# CAN_ChaseCar.net
KiCad netlist of a schematic drawn in Altium Designer
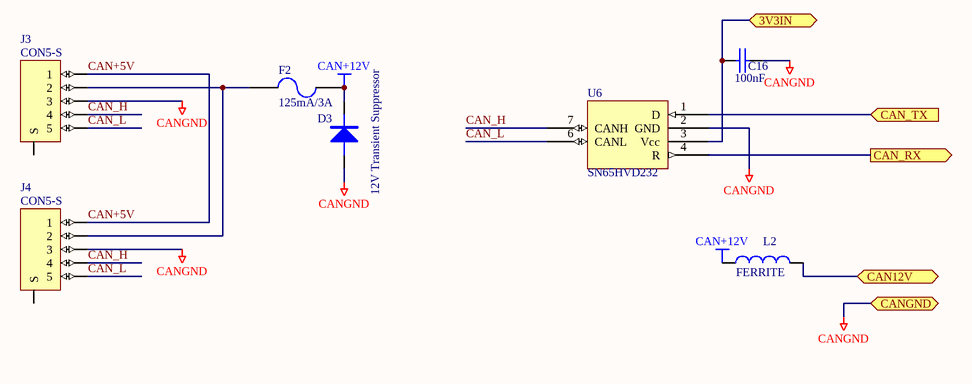
[diagram p0: CAN_ChaseCar.SchDoc]

(export (version "E")
  (design (tool "Eeschema 10.0.6"))
  (components
    (comp (ref "C16")
      (value "100nF")
      (footprint "0603")
      (description "Capacitor")
      (libsource (lib "*") (part "CAP"))
    )
    (comp (ref "D3")
      (value "12V Transient Suppressor")
      (footprint "SMA")
      (description "Diode")
      (libsource (lib "RCLDQ") (part "DIODE"))
    )
    (comp (ref "F2")
      (value "125mA/3A")
      (footprint "LITTELFUSE-154")
      (description "Fuse")
      (libsource (lib "*") (part "FUSE2"))
    )
    (comp (ref "J3")
      (value "CON5-S")
      (footprint "TRIAD5F")
      (description "Connector, 2 pin, with shield @ S")
      (libsource (lib "*") (part "CON5-S"))
    )
    (comp (ref "J4")
      (value "CON5-S")
      (footprint "TRIAD5F")
      (description "Connector, 2 pin, with shield @ S")
      (libsource (lib "*") (part "CON5-S"))
    )
    (comp (ref "L2")
      (value "FERRITE")
      (footprint "0603")
      (description "Inductor")
      (fields (field (name "MANUFACTURER") "Generic Components"))
      (libsource (lib "RCLDQ") (part "INDUCTOR"))
    )
    (comp (ref "U6")
      (value "SN65HVD232")
      (footprint "SO8")
      (description "3.3V CAN Transciever")
      (libsource (lib "*") (part "SN65HVD232"))
    )
  )
  (nets
    (net (code "1") (name "/3V3IN") (class "Default")
      (node (ref "C16") (pin "2") (pinfunction "2_2") (pintype "passive"))
      (node (ref "U6") (pin "3") (pinfunction "Vcc_3") (pintype "power_in"))
    )
    (net (code "2") (name "/CAN+5V") (class "Default")
      (node (ref "J3") (pin "1") (pinfunction "1_1") (pintype "bidirectional"))
      (node (ref "J4") (pin "1") (pinfunction "1_1") (pintype "bidirectional"))
    )
    (net (code "3") (name "/CAN12V") (class "Default")
      (node (ref "L2") (pin "2") (pinfunction "2_2") (pintype "passive"))
    )
    (net (code "4") (name "/CAN_H") (class "Default")
      (node (ref "J3") (pin "4") (pinfunction "4_4") (pintype "bidirectional"))
      (node (ref "J4") (pin "4") (pinfunction "4_4") (pintype "bidirectional"))
      (node (ref "U6") (pin "7") (pinfunction "CANH_7") (pintype "bidirectional"))
    )
    (net (code "5") (name "/CAN_L") (class "Default")
      (node (ref "J3") (pin "5") (pinfunction "5_5") (pintype "bidirectional"))
      (node (ref "J4") (pin "5") (pinfunction "5_5") (pintype "bidirectional"))
      (node (ref "U6") (pin "6") (pinfunction "CANL_6") (pintype "bidirectional"))
    )
    (net (code "6") (name "/CAN_RX") (class "Default")
      (node (ref "U6") (pin "4") (pinfunction "R_4") (pintype "output"))
    )
    (net (code "7") (name "/CAN_TX") (class "Default")
      (node (ref "U6") (pin "1") (pinfunction "D_1") (pintype "input"))
    )
    (net (code "8") (name "CAN+12V") (class "Default")
      (node (ref "D3") (pin "K") (pinfunction "K_K") (pintype "passive"))
      (node (ref "F2") (pin "2") (pinfunction "2_2") (pintype "passive"))
      (node (ref "L2") (pin "1") (pinfunction "1_1") (pintype "passive"))
    )
    (net (code "9") (name "CANGND") (class "Default")
      (node (ref "C16") (pin "1") (pinfunction "1_1") (pintype "passive"))
      (node (ref "D3") (pin "A") (pinfunction "A_A") (pintype "passive"))
      (node (ref "J3") (pin "3") (pinfunction "3_3") (pintype "bidirectional"))
      (node (ref "J4") (pin "3") (pinfunction "3_3") (pintype "bidirectional"))
      (node (ref "U6") (pin "2") (pinfunction "GND_2") (pintype "power_in"))
    )
    (net (code "10") (name "Net-(F2-Pad1)") (class "Default")
      (node (ref "F2") (pin "1") (pinfunction "1_1") (pintype "passive"))
      (node (ref "J3") (pin "2") (pinfunction "2_2") (pintype "bidirectional"))
      (node (ref "J4") (pin "2") (pinfunction "2_2") (pintype "bidirectional"))
    )
    (net (code "11") (name "unconnected-(J3-S-Pad0)") (class "Default")
      (node (ref "J3") (pin "0") (pinfunction "S_0") (pintype "bidirectional"))
    )
    (net (code "12") (name "unconnected-(J4-S-Pad0)") (class "Default")
      (node (ref "J4") (pin "0") (pinfunction "S_0") (pintype "bidirectional"))
    )
  )
)
